# v1_0.net
KiCad netlist of a schematic drawn in Altium Designer
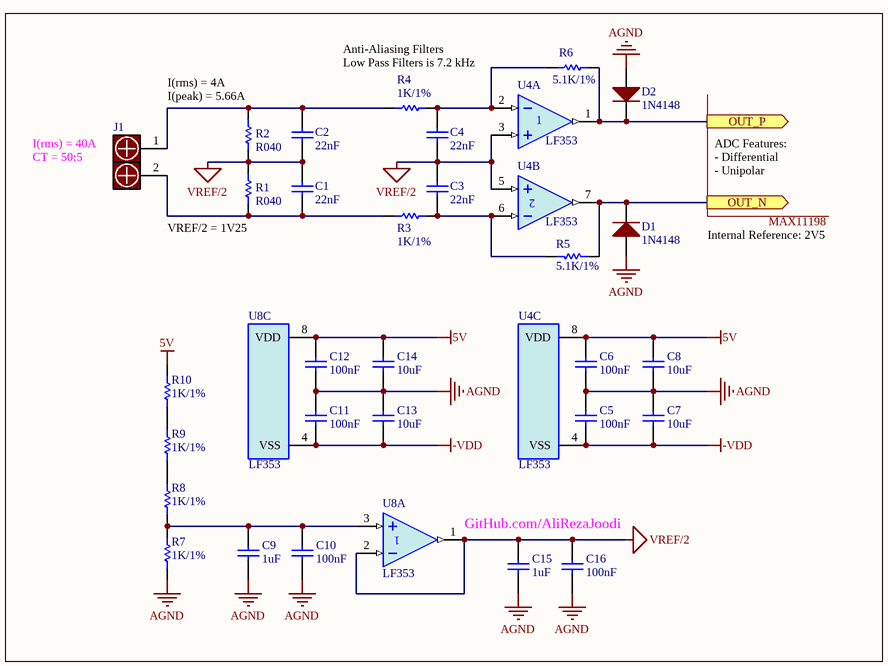
[diagram p0: v1.0.SchDoc]

(export (version "E")
  (design (tool "Eeschema 10.0.6"))
  (components
    (comp (ref "C1")
      (value "22nF")
      (footprint "Capacitor_Ceramic:SMD_0805")
      (description "Capacitor, Ceramic Multilayer, 25V, 10%")
      (libsource (lib "General") (part "Capacitor_Ceramic"))
    )
    (comp (ref "C2")
      (value "22nF")
      (footprint "Capacitor_Ceramic:SMD_0805")
      (description "Capacitor, Ceramic Multilayer, 25V, 10%")
      (libsource (lib "General") (part "Capacitor_Ceramic"))
    )
    (comp (ref "C3")
      (value "22nF")
      (footprint "Capacitor_Ceramic:SMD_0805")
      (description "Capacitor, Ceramic Multilayer, 25V, 10%")
      (libsource (lib "General") (part "Capacitor_Ceramic"))
    )
    (comp (ref "C4")
      (value "22nF")
      (footprint "Capacitor_Ceramic:SMD_0805")
      (description "Capacitor, Ceramic Multilayer, 25V, 10%")
      (libsource (lib "General") (part "Capacitor_Ceramic"))
    )
    (comp (ref "C5")
      (value "100nF")
      (footprint "Capacitor_Ceramic:SMD_0805")
      (description "Capacitor, Ceramic Multilayer, 25V, 10%")
      (libsource (lib "General") (part "Capacitor_Ceramic"))
    )
    (comp (ref "C6")
      (value "100nF")
      (footprint "Capacitor_Ceramic:SMD_0805")
      (description "Capacitor, Ceramic Multilayer, 25V, 10%")
      (libsource (lib "General") (part "Capacitor_Ceramic"))
    )
    (comp (ref "C7")
      (value "10uF")
      (footprint "Capacitor_Ceramic:SMD_0805")
      (description "Capacitor, Ceramic Multilayer, 25V, 10%")
      (libsource (lib "General") (part "Capacitor_Ceramic"))
    )
    (comp (ref "C8")
      (value "10uF")
      (footprint "Capacitor_Ceramic:SMD_0805")
      (description "Capacitor, Ceramic Multilayer, 25V, 10%")
      (libsource (lib "General") (part "Capacitor_Ceramic"))
    )
    (comp (ref "C9")
      (value "1uF")
      (footprint "Capacitor_Ceramic:SMD_0805")
      (description "Capacitor, Ceramic Multilayer, 25V, 10%")
      (libsource (lib "General") (part "Capacitor_Ceramic"))
    )
    (comp (ref "C10")
      (value "100nF")
      (footprint "Capacitor_Ceramic:SMD_0805")
      (description "Capacitor, Ceramic Multilayer, 25V, 10%")
      (libsource (lib "General") (part "Capacitor_Ceramic"))
    )
    (comp (ref "C11")
      (value "100nF")
      (footprint "Capacitor_Ceramic:SMD_0805")
      (description "Capacitor, Ceramic Multilayer, 25V, 10%")
      (libsource (lib "General") (part "Capacitor_Ceramic"))
    )
    (comp (ref "C12")
      (value "100nF")
      (footprint "Capacitor_Ceramic:SMD_0805")
      (description "Capacitor, Ceramic Multilayer, 25V, 10%")
      (libsource (lib "General") (part "Capacitor_Ceramic"))
    )
    (comp (ref "C13")
      (value "10uF")
      (footprint "Capacitor_Ceramic:SMD_0805")
      (description "Capacitor, Ceramic Multilayer, 25V, 10%")
      (libsource (lib "General") (part "Capacitor_Ceramic"))
    )
    (comp (ref "C14")
      (value "10uF")
      (footprint "Capacitor_Ceramic:SMD_0805")
      (description "Capacitor, Ceramic Multilayer, 25V, 10%")
      (libsource (lib "General") (part "Capacitor_Ceramic"))
    )
    (comp (ref "C15")
      (value "1uF")
      (footprint "Capacitor_Ceramic:SMD_0805")
      (description "Capacitor, Ceramic Multilayer, 25V, 10%")
      (libsource (lib "General") (part "Capacitor_Ceramic"))
    )
    (comp (ref "C16")
      (value "100nF")
      (footprint "Capacitor_Ceramic:SMD_0805")
      (description "Capacitor, Ceramic Multilayer, 25V, 10%")
      (libsource (lib "General") (part "Capacitor_Ceramic"))
    )
    (comp (ref "D1")
      (value "1N4148")
      (footprint "SMD_DO-213AA")
      (description "Diode")
      (fields (field (name "MANUFACTURER") "Microchip Technology") (field (name "PART NUMBER") "1N4148UR-1"))
      (libsource (lib "General") (part "Diode_2Form"))
    )
    (comp (ref "D2")
      (value "1N4148")
      (footprint "SMD_DO-213AA")
      (description "Diode")
      (fields (field (name "MANUFACTURER") "Microchip Technology") (field (name "PART NUMBER") "1N4148UR-1"))
      (libsource (lib "General") (part "Diode_2Form"))
    )
    (comp (ref "J1")
      (value "~")
      (footprint "1x2_P8.26")
      (description "Connector, Barrier Terminal Blocks, 2Pin")
      (fields (field (name "MANUFACTURER") "TE Connectivity") (field (name "PART NUMBER") "1977477-2"))
      (libsource (lib "Connector") (part "Connector1x2_Power_4Form"))
    )
    (comp (ref "R1")
      (value "R040")
      (footprint "SMD_4527")
      (description "Resistor, 2W, 1%")
      (fields (field (name "MANUFACTURER") "Vishay / Dale") (field (name "PART NUMBER") "WSR2R0400FEA"))
      (libsource (lib "") (part "Resistor_1"))
    )
    (comp (ref "R2")
      (value "R040")
      (footprint "SMD_4527")
      (description "Resistor, 2W, 1%")
      (fields (field (name "MANUFACTURER") "Vishay / Dale") (field (name "PART NUMBER") "WSR2R0400FEA"))
      (libsource (lib "") (part "Resistor_1"))
    )
    (comp (ref "R3")
      (value "1K/1%")
      (footprint "SMD_0805")
      (description "Resistor, 1/8W, 1%")
      (libsource (lib "General") (part "Resistor"))
    )
    (comp (ref "R4")
      (value "1K/1%")
      (footprint "SMD_0805")
      (description "Resistor, 1/8W, 1%")
      (libsource (lib "General") (part "Resistor"))
    )
    (comp (ref "R5")
      (value "5.1K/1%")
      (footprint "SMD_0805")
      (description "Resistor, 1/8W, 1%")
      (libsource (lib "General") (part "Resistor"))
    )
    (comp (ref "R6")
      (value "5.1K/1%")
      (footprint "SMD_0805")
      (description "Resistor, 1/8W, 1%")
      (libsource (lib "General") (part "Resistor"))
    )
    (comp (ref "R7")
      (value "1K/1%")
      (footprint "SMD_0805")
      (description "Resistor, 1/8W, 1%")
      (libsource (lib "General") (part "Resistor"))
    )
    (comp (ref "R8")
      (value "1K/1%")
      (footprint "SMD_0805")
      (description "Resistor, 1/8W, 1%")
      (libsource (lib "General") (part "Resistor"))
    )
    (comp (ref "R9")
      (value "1K/1%")
      (footprint "SMD_0805")
      (description "Resistor, 1/8W, 1%")
      (libsource (lib "General") (part "Resistor"))
    )
    (comp (ref "R10")
      (value "1K/1%")
      (footprint "SMD_0805")
      (description "Resistor, 1/8W, 1%")
      (libsource (lib "General") (part "Resistor"))
    )
    (comp (ref "U4")
      (value "LF353")
      (footprint "SOIC127P600-8CM")
      (description "IC, Op-Amp")
      (fields (field (name "MANUFACTURER") "Texas Instruments") (field (name "PART NUMBER") "LF353P"))
      (libsource (lib "IC_OpAmp") (part "Op-Amp_Form1"))
    )
    (comp (ref "U8")
      (value "LF353")
      (footprint "SOIC127P600-8CM")
      (description "IC, Op-Amp")
      (fields (field (name "MANUFACTURER") "Texas Instruments") (field (name "PART NUMBER") "LF353P"))
      (libsource (lib "IC_OpAmp") (part "Op-Amp_Form1"))
    )
  )
  (nets
    (net (code "1") (name "-VDD") (class "Default")
      (node (ref "C11") (pin "1") (pinfunction "1_1") (pintype "passive"))
      (node (ref "C13") (pin "2") (pinfunction "2_2") (pintype "passive"))
      (node (ref "C5") (pin "1") (pinfunction "1_1") (pintype "passive"))
      (node (ref "C7") (pin "2") (pinfunction "2_2") (pintype "passive"))
      (node (ref "U4") (pin "4") (pinfunction "VSS_4") (pintype "power_in"))
      (node (ref "U8") (pin "4") (pinfunction "VSS_4") (pintype "power_in"))
    )
    (net (code "2") (name "/OUT_N") (class "Default")
      (node (ref "D1") (pin "2") (pinfunction "K_2") (pintype "passive"))
      (node (ref "R5") (pin "1") (pinfunction "1_1") (pintype "passive"))
      (node (ref "U4") (pin "7") (pinfunction "OUT_7") (pintype "output"))
    )
    (net (code "3") (name "/OUT_P") (class "Default")
      (node (ref "D2") (pin "2") (pinfunction "K_2") (pintype "passive"))
      (node (ref "R6") (pin "1") (pinfunction "1_1") (pintype "passive"))
      (node (ref "U4") (pin "1") (pinfunction "OUT_1") (pintype "output"))
    )
    (net (code "4") (name "5V") (class "Default")
      (node (ref "C12") (pin "2") (pinfunction "2_2") (pintype "passive"))
      (node (ref "C14") (pin "1") (pinfunction "1_1") (pintype "passive"))
      (node (ref "C6") (pin "2") (pinfunction "2_2") (pintype "passive"))
      (node (ref "C8") (pin "1") (pinfunction "1_1") (pintype "passive"))
      (node (ref "R10") (pin "1") (pinfunction "1_1") (pintype "passive"))
      (node (ref "U4") (pin "8") (pinfunction "VDD_8") (pintype "passive"))
      (node (ref "U8") (pin "8") (pinfunction "VDD_8") (pintype "passive"))
    )
    (net (code "5") (name "AGND") (class "Default")
      (node (ref "C10") (pin "1") (pinfunction "1_1") (pintype "passive"))
      (node (ref "C11") (pin "2") (pinfunction "2_2") (pintype "passive"))
      (node (ref "C12") (pin "1") (pinfunction "1_1") (pintype "passive"))
      (node (ref "C13") (pin "1") (pinfunction "1_1") (pintype "passive"))
      (node (ref "C14") (pin "2") (pinfunction "2_2") (pintype "passive"))
      (node (ref "C15") (pin "2") (pinfunction "2_2") (pintype "passive"))
      (node (ref "C16") (pin "1") (pinfunction "1_1") (pintype "passive"))
      (node (ref "C5") (pin "2") (pinfunction "2_2") (pintype "passive"))
      (node (ref "C6") (pin "1") (pinfunction "1_1") (pintype "passive"))
      (node (ref "C7") (pin "1") (pinfunction "1_1") (pintype "passive"))
      (node (ref "C8") (pin "2") (pinfunction "2_2") (pintype "passive"))
      (node (ref "C9") (pin "2") (pinfunction "2_2") (pintype "passive"))
      (node (ref "D1") (pin "1") (pinfunction "A_1") (pintype "passive"))
      (node (ref "D2") (pin "1") (pinfunction "A_1") (pintype "passive"))
      (node (ref "R7") (pin "2") (pinfunction "2_2") (pintype "passive"))
    )
    (net (code "6") (name "Net-(C1-Pad2)") (class "Default")
      (node (ref "C1") (pin "2") (pinfunction "2_2") (pintype "passive"))
      (node (ref "J1") (pin "2") (pinfunction "2_2") (pintype "passive"))
      (node (ref "R1") (pin "1") (pinfunction "1_1") (pintype "passive"))
      (node (ref "R3") (pin "2") (pinfunction "2_2") (pintype "passive"))
    )
    (net (code "7") (name "Net-(C2-Pad1)") (class "Default")
      (node (ref "C2") (pin "1") (pinfunction "1_1") (pintype "passive"))
      (node (ref "J1") (pin "1") (pinfunction "1_1") (pintype "passive"))
      (node (ref "R2") (pin "2") (pinfunction "2_2") (pintype "passive"))
      (node (ref "R4") (pin "2") (pinfunction "2_2") (pintype "passive"))
    )
    (net (code "8") (name "Net-(R8-Pad1)") (class "Default")
      (node (ref "R8") (pin "1") (pinfunction "1_1") (pintype "passive"))
      (node (ref "R9") (pin "2") (pinfunction "2_2") (pintype "passive"))
    )
    (net (code "9") (name "Net-(R10-Pad2)") (class "Default")
      (node (ref "R10") (pin "2") (pinfunction "2_2") (pintype "passive"))
      (node (ref "R9") (pin "1") (pinfunction "1_1") (pintype "passive"))
    )
    (net (code "10") (name "Net-(U4A-IN-)") (class "Default")
      (node (ref "C4") (pin "1") (pinfunction "1_1") (pintype "passive"))
      (node (ref "R4") (pin "1") (pinfunction "1_1") (pintype "passive"))
      (node (ref "R6") (pin "2") (pinfunction "2_2") (pintype "passive"))
      (node (ref "U4") (pin "2") (pinfunction "IN-_2") (pintype "input"))
    )
    (net (code "11") (name "Net-(U4B-IN-)") (class "Default")
      (node (ref "C3") (pin "2") (pinfunction "2_2") (pintype "passive"))
      (node (ref "R3") (pin "1") (pinfunction "1_1") (pintype "passive"))
      (node (ref "R5") (pin "2") (pinfunction "2_2") (pintype "passive"))
      (node (ref "U4") (pin "6") (pinfunction "IN-_6") (pintype "input"))
    )
    (net (code "12") (name "Net-(U8A-IN+)") (class "Default")
      (node (ref "C10") (pin "2") (pinfunction "2_2") (pintype "passive"))
      (node (ref "C9") (pin "1") (pinfunction "1_1") (pintype "passive"))
      (node (ref "R7") (pin "1") (pinfunction "1_1") (pintype "passive"))
      (node (ref "R8") (pin "2") (pinfunction "2_2") (pintype "passive"))
      (node (ref "U8") (pin "3") (pinfunction "IN+_3") (pintype "input"))
    )
    (net (code "13") (name "VREF{slash}2") (class "Default")
      (node (ref "C1") (pin "1") (pinfunction "1_1") (pintype "passive"))
      (node (ref "C15") (pin "1") (pinfunction "1_1") (pintype "passive"))
      (node (ref "C16") (pin "2") (pinfunction "2_2") (pintype "passive"))
      (node (ref "C2") (pin "2") (pinfunction "2_2") (pintype "passive"))
      (node (ref "C3") (pin "1") (pinfunction "1_1") (pintype "passive"))
      (node (ref "C4") (pin "2") (pinfunction "2_2") (pintype "passive"))
      (node (ref "R1") (pin "2") (pinfunction "2_2") (pintype "passive"))
      (node (ref "R2") (pin "1") (pinfunction "1_1") (pintype "passive"))
      (node (ref "U4") (pin "3") (pinfunction "IN+_3") (pintype "input"))
      (node (ref "U4") (pin "5") (pinfunction "IN+_5") (pintype "input"))
      (node (ref "U8") (pin "1") (pinfunction "OUT_1") (pintype "output"))
      (node (ref "U8") (pin "2") (pinfunction "IN-_2") (pintype "input"))
    )
  )
)
